# SCH_One.net
KiCad netlist of a schematic drawn in Altium Designer
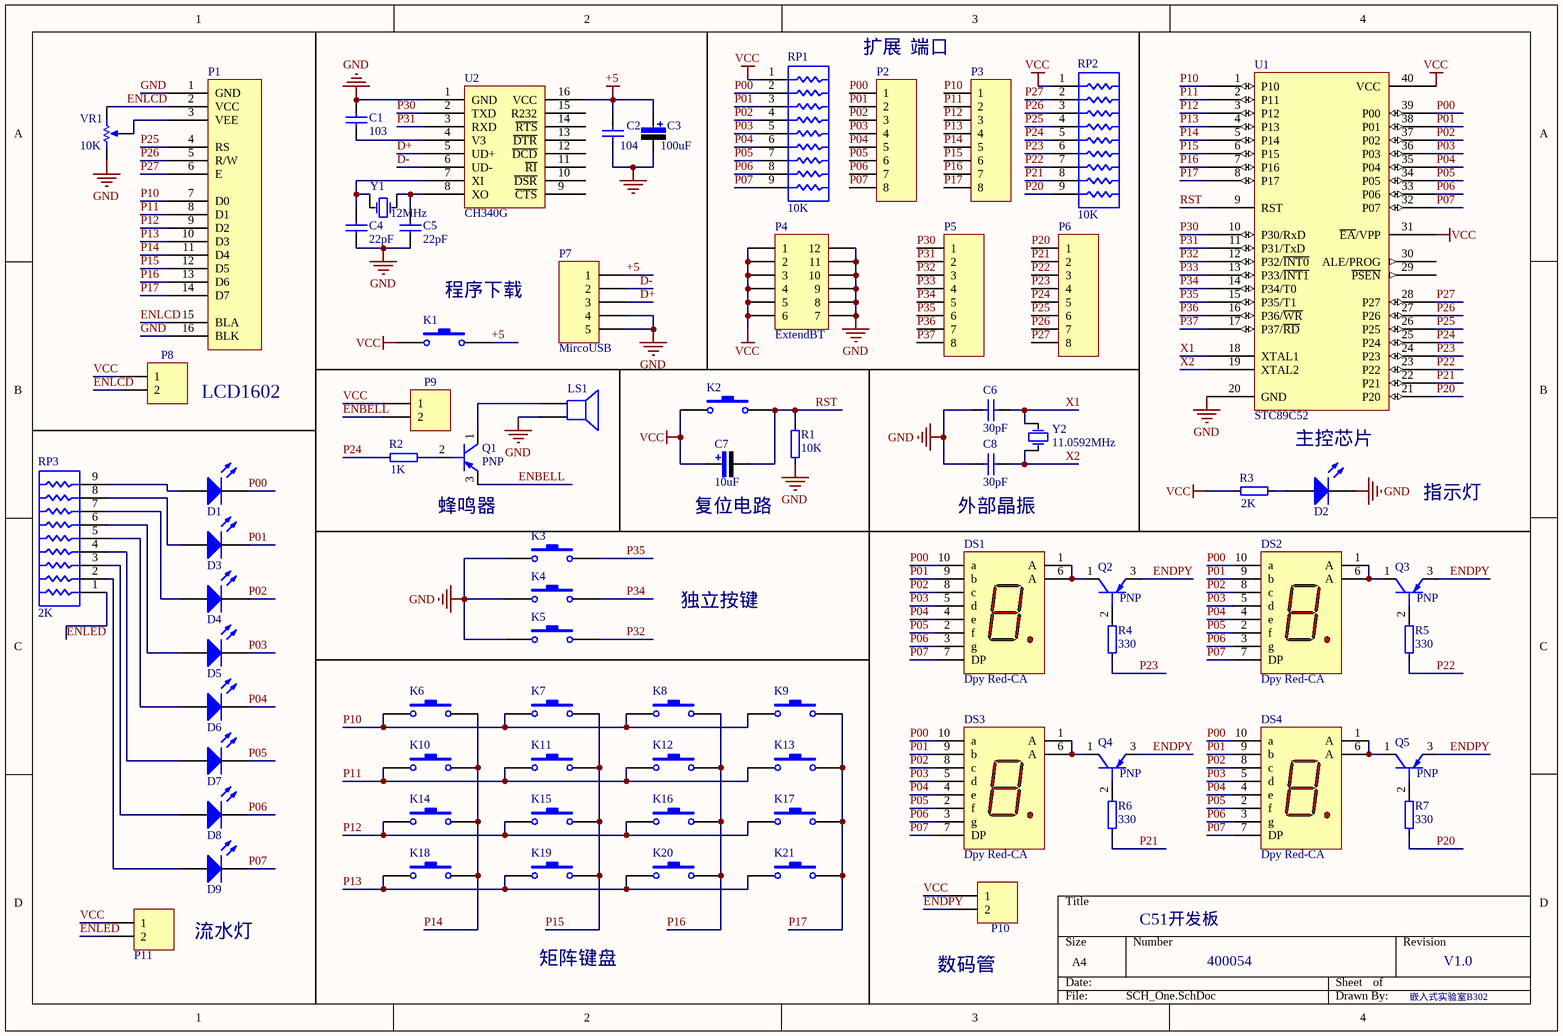
[diagram p0: SCH_One.SchDoc]

(export (version "E")
  (design (tool "Eeschema 10.0.6"))
  (components
    (comp (ref "C1")
      (value "103")
      (footprint "C-RAD")
      (description "电容")
      (libsource (lib "MyLibrary") (part "Cap1"))
    )
    (comp (ref "C2")
      (value "104")
      (footprint "C-RAD")
      (description "电容")
      (libsource (lib "MyLibrary") (part "Cap1"))
    )
    (comp (ref "C3")
      (value "100uF")
      (footprint "CAP_100uF")
      (description "极性电解电容")
      (fields (field (name "Comment") "Cap Pol") (field (name "PUBLISHER") "Altium Limited"))
      (libsource (lib "") (part "Cap Pol_1"))
    )
    (comp (ref "C4")
      (value "22pF")
      (footprint "C-RAD")
      (description "电容")
      (libsource (lib "MyLibrary") (part "Cap1"))
    )
    (comp (ref "C5")
      (value "22pF")
      (footprint "C-RAD")
      (description "电容")
      (libsource (lib "MyLibrary") (part "Cap1"))
    )
    (comp (ref "C6")
      (value "30pF")
      (footprint "C-RAD")
      (description "电容")
      (libsource (lib "MyLibrary") (part "Cap1"))
    )
    (comp (ref "C7")
      (value "10uF")
      (footprint "CAP_10uF")
      (description "极性电解电容")
      (fields (field (name "Comment") "Cap Pol") (field (name "PUBLISHER") "Altium Limited"))
      (libsource (lib "Library") (part "Cap Pol"))
    )
    (comp (ref "C8")
      (value "30pF")
      (footprint "C-RAD")
      (description "电容")
      (libsource (lib "MyLibrary") (part "Cap1"))
    )
    (comp (ref "D1")
      (value "LED0")
      (footprint "LED3")
      (description "发光二极管")
      (fields (field (name "PUBLISHER") "Altium Limited"))
      (libsource (lib "Library") (part "LED0"))
    )
    (comp (ref "D2")
      (value "LED0")
      (footprint "LED3")
      (description "发光二极管")
      (fields (field (name "PUBLISHER") "Altium Limited"))
      (libsource (lib "Library") (part "LED0"))
    )
    (comp (ref "D3")
      (value "LED0")
      (footprint "LED3")
      (description "发光二极管")
      (fields (field (name "PUBLISHER") "Altium Limited"))
      (libsource (lib "Library") (part "LED0"))
    )
    (comp (ref "D4")
      (value "LED0")
      (footprint "LED3")
      (description "发光二极管")
      (fields (field (name "PUBLISHER") "Altium Limited"))
      (libsource (lib "Library") (part "LED0"))
    )
    (comp (ref "D5")
      (value "LED0")
      (footprint "LED3")
      (description "发光二极管")
      (fields (field (name "PUBLISHER") "Altium Limited"))
      (libsource (lib "Library") (part "LED0"))
    )
    (comp (ref "D6")
      (value "LED0")
      (footprint "LED3")
      (description "发光二极管")
      (fields (field (name "PUBLISHER") "Altium Limited"))
      (libsource (lib "Library") (part "LED0"))
    )
    (comp (ref "D7")
      (value "LED0")
      (footprint "LED3")
      (description "发光二极管")
      (fields (field (name "PUBLISHER") "Altium Limited"))
      (libsource (lib "Library") (part "LED0"))
    )
    (comp (ref "D8")
      (value "LED0")
      (footprint "LED3")
      (description "发光二极管")
      (fields (field (name "PUBLISHER") "Altium Limited"))
      (libsource (lib "Library") (part "LED0"))
    )
    (comp (ref "D9")
      (value "LED0")
      (footprint "LED3")
      (description "发光二极管")
      (fields (field (name "PUBLISHER") "Altium Limited"))
      (libsource (lib "Library") (part "LED0"))
    )
    (comp (ref "DS1")
      (value "Dpy Red-CA")
      (footprint "A")
      (description "7.62 mm Black Surface HER 7-Segment Display: CA, RH DP")
      (fields (field (name "PUBLISHER") "Altium Limited"))
      (libsource (lib "Miscellaneous Devices") (part "Dpy Red-CA"))
    )
    (comp (ref "DS2")
      (value "Dpy Red-CA")
      (footprint "A")
      (description "7.62 mm Black Surface HER 7-Segment Display: CA, RH DP")
      (fields (field (name "PUBLISHER") "Altium Limited"))
      (libsource (lib "Miscellaneous Devices") (part "Dpy Red-CA"))
    )
    (comp (ref "DS3")
      (value "Dpy Red-CA")
      (footprint "A")
      (description "7.62 mm Black Surface HER 7-Segment Display: CA, RH DP")
      (fields (field (name "PUBLISHER") "Altium Limited"))
      (libsource (lib "Miscellaneous Devices") (part "Dpy Red-CA"))
    )
    (comp (ref "DS4")
      (value "Dpy Red-CA")
      (footprint "A")
      (description "7.62 mm Black Surface HER 7-Segment Display: CA, RH DP")
      (fields (field (name "PUBLISHER") "Altium Limited"))
      (libsource (lib "Miscellaneous Devices") (part "Dpy Red-CA"))
    )
    (comp (ref "K1")
      (value "Switch1")
      (footprint "KEY-6")
      (description "按键/单刀单掷开关")
      (libsource (lib "MyLibrary") (part "Switch1"))
    )
    (comp (ref "K2")
      (value "Switch1")
      (footprint "SW_PB - 6.5x4.5")
      (description "按键/单刀单掷开关")
      (libsource (lib "MyLibrary") (part "Switch1"))
    )
    (comp (ref "K3")
      (value "Switch1")
      (footprint "SW_PB - 6.5x4.5")
      (description "按键/单刀单掷开关")
      (libsource (lib "MyLibrary") (part "Switch1"))
    )
    (comp (ref "K4")
      (value "Switch1")
      (footprint "SW_PB - 6.5x4.5")
      (description "按键/单刀单掷开关")
      (libsource (lib "MyLibrary") (part "Switch1"))
    )
    (comp (ref "K5")
      (value "Switch1")
      (footprint "SW_PB - 6.5x4.5")
      (description "按键/单刀单掷开关")
      (libsource (lib "MyLibrary") (part "Switch1"))
    )
    (comp (ref "K6")
      (value "Switch1")
      (footprint "SW_PB - 6.5x4.5")
      (description "按键/单刀单掷开关")
      (libsource (lib "MyLibrary") (part "Switch1"))
    )
    (comp (ref "K7")
      (value "Switch1")
      (footprint "SW_PB - 6.5x4.5")
      (description "按键/单刀单掷开关")
      (libsource (lib "MyLibrary") (part "Switch1"))
    )
    (comp (ref "K8")
      (value "Switch1")
      (footprint "SW_PB - 6.5x4.5")
      (description "按键/单刀单掷开关")
      (libsource (lib "MyLibrary") (part "Switch1"))
    )
    (comp (ref "K9")
      (value "Switch1")
      (footprint "SW_PB - 6.5x4.5")
      (description "按键/单刀单掷开关")
      (libsource (lib "MyLibrary") (part "Switch1"))
    )
    (comp (ref "K10")
      (value "Switch1")
      (footprint "SW_PB - 6.5x4.5")
      (description "按键/单刀单掷开关")
      (libsource (lib "MyLibrary") (part "Switch1"))
    )
    (comp (ref "K11")
      (value "Switch1")
      (footprint "SW_PB - 6.5x4.5")
      (description "按键/单刀单掷开关")
      (libsource (lib "MyLibrary") (part "Switch1"))
    )
    (comp (ref "K12")
      (value "Switch1")
      (footprint "SW_PB - 6.5x4.5")
      (description "按键/单刀单掷开关")
      (libsource (lib "MyLibrary") (part "Switch1"))
    )
    (comp (ref "K13")
      (value "Switch1")
      (footprint "SW_PB - 6.5x4.5")
      (description "按键/单刀单掷开关")
      (libsource (lib "MyLibrary") (part "Switch1"))
    )
    (comp (ref "K14")
      (value "Switch1")
      (footprint "SW_PB - 6.5x4.5")
      (description "按键/单刀单掷开关")
      (libsource (lib "MyLibrary") (part "Switch1"))
    )
    (comp (ref "K15")
      (value "Switch1")
      (footprint "SW_PB - 6.5x4.5")
      (description "按键/单刀单掷开关")
      (libsource (lib "MyLibrary") (part "Switch1"))
    )
    (comp (ref "K16")
      (value "Switch1")
      (footprint "SW_PB - 6.5x4.5")
      (description "按键/单刀单掷开关")
      (libsource (lib "MyLibrary") (part "Switch1"))
    )
    (comp (ref "K17")
      (value "Switch1")
      (footprint "SW_PB - 6.5x4.5")
      (description "按键/单刀单掷开关")
      (libsource (lib "MyLibrary") (part "Switch1"))
    )
    (comp (ref "K18")
      (value "Switch1")
      (footprint "SW_PB - 6.5x4.5")
      (description "按键/单刀单掷开关")
      (libsource (lib "MyLibrary") (part "Switch1"))
    )
    (comp (ref "K19")
      (value "Switch1")
      (footprint "SW_PB - 6.5x4.5")
      (description "按键/单刀单掷开关")
      (libsource (lib "MyLibrary") (part "Switch1"))
    )
    (comp (ref "K20")
      (value "Switch1")
      (footprint "SW_PB - 6.5x4.5")
      (description "按键/单刀单掷开关")
      (libsource (lib "MyLibrary") (part "Switch1"))
    )
    (comp (ref "K21")
      (value "Switch1")
      (footprint "SW_PB - 6.5x4.5")
      (description "按键/单刀单掷开关")
      (libsource (lib "MyLibrary") (part "Switch1"))
    )
    (comp (ref "LS1") (value "SPEAKER") (footprint "Beep") (libsource (lib "SCH") (part "SPEAKER")))
    (comp (ref "P1")
      (value "~")
      (footprint "SIP16")
      (description "1602液晶显示器")
      (libsource (lib "MyLibrary") (part "1602"))
    )
    (comp (ref "P2")
      (value "Header 8")
      (footprint "SIP8 - duplicate")
      (description "8PIN")
      (libsource (lib "MyLibrary") (part "Header 8"))
    )
    (comp (ref "P3")
      (value "Header 8")
      (footprint "SIP8 - duplicate")
      (description "8PIN")
      (libsource (lib "MyLibrary") (part "Header 8"))
    )
    (comp (ref "P4")
      (value "ExtendBT")
      (footprint "HDR2x6")
      (description "6PIN两排")
      (libsource (lib "PCB_One") (part "Header 6x2"))
    )
    (comp (ref "P5")
      (value "Header 8")
      (footprint "SIP8")
      (description "8PIN")
      (libsource (lib "MyLibrary") (part "Header 8"))
    )
    (comp (ref "P6")
      (value "Header 8")
      (footprint "SIP8 - duplicate")
      (description "8PIN")
      (libsource (lib "MyLibrary") (part "Header 8"))
    )
    (comp (ref "P7")
      (value "MircoUSB")
      (footprint "MircoUSB")
      (description "5PIN")
      (libsource (lib "MyLibrary") (part "Header 5"))
    )
    (comp (ref "P8")
      (value "Header 2")
      (footprint "HDR2X1_A")
      (description "接插件")
      (fields (field (name "PUBLISHER") "Altium Limited"))
      (libsource (lib "PCB_One") (part "Header 2"))
    )
    (comp (ref "P9")
      (value "Header 2")
      (footprint "HDR2X1_A")
      (description "接插件")
      (fields (field (name "PUBLISHER") "Altium Limited"))
      (libsource (lib "PCB_One") (part "Header 2"))
    )
    (comp (ref "P10")
      (value "Header 2")
      (footprint "HDR2X1_A")
      (description "接插件")
      (fields (field (name "PUBLISHER") "Altium Limited"))
      (libsource (lib "PCB_One") (part "Header 2"))
    )
    (comp (ref "P11")
      (value "Header 2")
      (footprint "HDR2X1_A")
      (description "接插件")
      (fields (field (name "PUBLISHER") "Altium Limited"))
      (libsource (lib "PCB_One") (part "Header 2"))
    )
    (comp (ref "Q1")
      (value "PNP")
      (footprint "TO-92")
      (description "PNP Transistor")
      (libsource (lib "SCH") (part "PNP"))
    )
    (comp (ref "Q2")
      (value "PNP")
      (footprint "TO-92")
      (description "PNP Transistor")
      (libsource (lib "SCH") (part "PNP"))
    )
    (comp (ref "Q3")
      (value "PNP")
      (footprint "TO-92")
      (description "PNP Transistor")
      (libsource (lib "SCH") (part "PNP"))
    )
    (comp (ref "Q4")
      (value "PNP")
      (footprint "TO-92")
      (description "PNP Transistor")
      (libsource (lib "SCH") (part "PNP"))
    )
    (comp (ref "Q5")
      (value "PNP")
      (footprint "TO-92")
      (description "PNP Transistor")
      (libsource (lib "SCH") (part "PNP"))
    )
    (comp (ref "R1")
      (value "10K")
      (footprint "Res_DIP")
      (description "直插电阻")
      (fields (field (name "Comment") "Res"))
      (libsource (lib "MY_Lib") (part "Res"))
    )
    (comp (ref "R2")
      (value "1K")
      (footprint "Res_DIP")
      (description "直插电阻")
      (fields (field (name "Comment") "Res"))
      (libsource (lib "MY_Lib") (part "Res"))
    )
    (comp (ref "R3")
      (value "2K")
      (footprint "Res_DIP")
      (description "直插电阻")
      (fields (field (name "Comment") "Res"))
      (libsource (lib "MY_Lib") (part "Res"))
    )
    (comp (ref "R4")
      (value "330")
      (footprint "Res_DIP")
      (description "直插电阻")
      (fields (field (name "Comment") "Res"))
      (libsource (lib "MY_Lib") (part "Res"))
    )
    (comp (ref "R5")
      (value "330")
      (footprint "Res_DIP")
      (description "直插电阻")
      (fields (field (name "Comment") "Res"))
      (libsource (lib "MY_Lib") (part "Res"))
    )
    (comp (ref "R6")
      (value "330")
      (footprint "Res_DIP")
      (description "直插电阻")
      (fields (field (name "Comment") "Res"))
      (libsource (lib "MY_Lib") (part "Res"))
    )
    (comp (ref "R7")
      (value "330")
      (footprint "Res_DIP")
      (description "直插电阻")
      (fields (field (name "Comment") "Res"))
      (libsource (lib "MY_Lib") (part "Res"))
    )
    (comp (ref "RP1")
      (value "10K")
      (footprint "SIP9 - duplicate")
      (description "9PIN排阻")
      (libsource (lib "MyLibrary") (part "Res Pack2"))
    )
    (comp (ref "RP2")
      (value "10K")
      (footprint "SIP9 - duplicate")
      (description "9PIN排阻")
      (libsource (lib "MyLibrary") (part "Res Pack2"))
    )
    (comp (ref "RP3")
      (value "2K")
      (footprint "SIP9 - duplicate")
      (description "9PIN排阻")
      (libsource (lib "MyLibrary") (part "Res Pack2"))
    )
    (comp (ref "U1")
      (value "STC89C52")
      (footprint "DIP40")
      (description "C51单片机")
      (libsource (lib "MyLibrary") (part "AT89C51"))
    )
    (comp (ref "U2")
      (value "CH340G")
      (footprint "PCB贴片元件封装库:SOP-16")
      (description "USB-SERIAL")
      (libsource (lib "迷宫机器人") (part "CH340G"))
    )
    (comp (ref "VR1")
      (value "10K")
      (footprint "VR4")
      (description "可变电阻器")
      (libsource (lib "MyLibrary") (part "VR"))
    )
    (comp (ref "Y1")
      (value "12MHz")
      (footprint "XTAL1")
      (description "晶振")
      (fields (field (name "Comment") "XTAL") (field (name "PUBLISHER") "Altium Limited"))
      (libsource (lib "Library") (part "XTAL"))
    )
    (comp (ref "Y2")
      (value "11.0592MHz")
      (footprint "XTAL1")
      (description "晶振")
      (fields (field (name "Comment") "XTAL") (field (name "PUBLISHER") "Altium Limited"))
      (libsource (lib "Library") (part "XTAL"))
    )
  )
  (nets
    (net (code "1") (name "+5") (class "Default")
      (node (ref "C2") (pin "2") (pinfunction "2_2") (pintype "passive"))
      (node (ref "C3") (pin "1") (pinfunction "1_1") (pintype "passive"))
      (node (ref "K1") (pin "2") (pinfunction "2_2") (pintype "passive"))
      (node (ref "P7") (pin "1") (pinfunction "1_1") (pintype "passive"))
      (node (ref "U2") (pin "16") (pinfunction "VCC_16") (pintype "passive"))
    )
    (net (code "2") (name "/D+") (class "Default")
      (node (ref "P7") (pin "3") (pinfunction "3_3") (pintype "passive"))
      (node (ref "U2") (pin "5") (pinfunction "UD+_5") (pintype "passive"))
    )
    (net (code "3") (name "/D-") (class "Default")
      (node (ref "P7") (pin "2") (pinfunction "2_2") (pintype "passive"))
      (node (ref "U2") (pin "6") (pinfunction "UD-_6") (pintype "passive"))
    )
    (net (code "4") (name "/ENBELL") (class "Default")
      (node (ref "P9") (pin "2") (pinfunction "2_2") (pintype "passive"))
      (node (ref "Q1") (pin "3") (pinfunction "EMITTER_3") (pintype "open_emitter"))
    )
    (net (code "5") (name "/ENDPY") (class "Default")
      (node (ref "P10") (pin "2") (pinfunction "2_2") (pintype "passive"))
      (node (ref "Q2") (pin "3") (pinfunction "EMITTER_3") (pintype "open_emitter"))
      (node (ref "Q3") (pin "3") (pinfunction "EMITTER_3") (pintype "open_emitter"))
      (node (ref "Q4") (pin "3") (pinfunction "EMITTER_3") (pintype "open_emitter"))
      (node (ref "Q5") (pin "3") (pinfunction "EMITTER_3") (pintype "open_emitter"))
    )
    (net (code "6") (name "/ENLCD") (class "Default")
      (node (ref "P1") (pin "15") (pinfunction "BLA_15") (pintype "passive"))
      (node (ref "P1") (pin "2") (pinfunction "VCC_2") (pintype "passive"))
      (node (ref "P8") (pin "2") (pinfunction "2_2") (pintype "passive"))
      (node (ref "VR1") (pin "1") (pinfunction "TOP_1") (pintype "passive"))
    )
    (net (code "7") (name "/ENLED") (class "Default")
      (node (ref "P11") (pin "2") (pinfunction "2_2") (pintype "passive"))
      (node (ref "RP3") (pin "1") (pinfunction "1_1") (pintype "passive"))
    )
    (net (code "8") (name "/P00") (class "Default")
      (node (ref "D1") (pin "K") (pinfunction "K_K") (pintype "passive"))
      (node (ref "DS1") (pin "10") (pinfunction "a_10") (pintype "passive"))
      (node (ref "DS2") (pin "10") (pinfunction "a_10") (pintype "passive"))
      (node (ref "DS3") (pin "10") (pinfunction "a_10") (pintype "passive"))
      (node (ref "DS4") (pin "10") (pinfunction "a_10") (pintype "passive"))
      (node (ref "P2") (pin "1") (pinfunction "1_1") (pintype "passive"))
      (node (ref "RP1") (pin "2") (pinfunction "2_2") (pintype "passive"))
      (node (ref "U1") (pin "39") (pinfunction "P00_39") (pintype "bidirectional"))
    )
    (net (code "9") (name "/P01") (class "Default")
      (node (ref "D3") (pin "K") (pinfunction "K_K") (pintype "passive"))
      (node (ref "DS1") (pin "9") (pinfunction "b_9") (pintype "passive"))
      (node (ref "DS2") (pin "9") (pinfunction "b_9") (pintype "passive"))
      (node (ref "DS3") (pin "9") (pinfunction "b_9") (pintype "passive"))
      (node (ref "DS4") (pin "9") (pinfunction "b_9") (pintype "passive"))
      (node (ref "P2") (pin "2") (pinfunction "2_2") (pintype "passive"))
      (node (ref "RP1") (pin "3") (pinfunction "3_3") (pintype "passive"))
      (node (ref "U1") (pin "38") (pinfunction "P01_38") (pintype "bidirectional"))
    )
    (net (code "10") (name "/P02") (class "Default")
      (node (ref "D4") (pin "K") (pinfunction "K_K") (pintype "passive"))
      (node (ref "DS1") (pin "8") (pinfunction "c_8") (pintype "passive"))
      (node (ref "DS2") (pin "8") (pinfunction "c_8") (pintype "passive"))
      (node (ref "DS3") (pin "8") (pinfunction "c_8") (pintype "passive"))
      (node (ref "DS4") (pin "8") (pinfunction "c_8") (pintype "passive"))
      (node (ref "P2") (pin "3") (pinfunction "3_3") (pintype "passive"))
      (node (ref "RP1") (pin "4") (pinfunction "4_4") (pintype "passive"))
      (node (ref "U1") (pin "37") (pinfunction "P02_37") (pintype "bidirectional"))
    )
    (net (code "11") (name "/P03") (class "Default")
      (node (ref "D5") (pin "K") (pinfunction "K_K") (pintype "passive"))
      (node (ref "DS1") (pin "5") (pinfunction "d_5") (pintype "passive"))
      (node (ref "DS2") (pin "5") (pinfunction "d_5") (pintype "passive"))
      (node (ref "DS3") (pin "5") (pinfunction "d_5") (pintype "passive"))
      (node (ref "DS4") (pin "5") (pinfunction "d_5") (pintype "passive"))
      (node (ref "P2") (pin "4") (pinfunction "4_4") (pintype "passive"))
      (node (ref "RP1") (pin "5") (pinfunction "5_5") (pintype "passive"))
      (node (ref "U1") (pin "36") (pinfunction "P03_36") (pintype "bidirectional"))
    )
    (net (code "12") (name "/P04") (class "Default")
      (node (ref "D6") (pin "K") (pinfunction "K_K") (pintype "passive"))
      (node (ref "DS1") (pin "4") (pinfunction "e_4") (pintype "passive"))
      (node (ref "DS2") (pin "4") (pinfunction "e_4") (pintype "passive"))
      (node (ref "DS3") (pin "4") (pinfunction "e_4") (pintype "passive"))
      (node (ref "DS4") (pin "4") (pinfunction "e_4") (pintype "passive"))
      (node (ref "P2") (pin "5") (pinfunction "5_5") (pintype "passive"))
      (node (ref "RP1") (pin "6") (pinfunction "6_6") (pintype "passive"))
      (node (ref "U1") (pin "35") (pinfunction "P04_35") (pintype "bidirectional"))
    )
    (net (code "13") (name "/P05") (class "Default")
      (node (ref "D7") (pin "K") (pinfunction "K_K") (pintype "passive"))
      (node (ref "DS1") (pin "2") (pinfunction "f_2") (pintype "passive"))
      (node (ref "DS2") (pin "2") (pinfunction "f_2") (pintype "passive"))
      (node (ref "DS3") (pin "2") (pinfunction "f_2") (pintype "passive"))
      (node (ref "DS4") (pin "2") (pinfunction "f_2") (pintype "passive"))
      (node (ref "P2") (pin "6") (pinfunction "6_6") (pintype "passive"))
      (node (ref "RP1") (pin "7") (pinfunction "7_7") (pintype "passive"))
      (node (ref "U1") (pin "34") (pinfunction "P05_34") (pintype "bidirectional"))
    )
    (net (code "14") (name "/P06") (class "Default")
      (node (ref "D8") (pin "K") (pinfunction "K_K") (pintype "passive"))
      (node (ref "DS1") (pin "3") (pinfunction "g_3") (pintype "passive"))
      (node (ref "DS2") (pin "3") (pinfunction "g_3") (pintype "passive"))
      (node (ref "DS3") (pin "3") (pinfunction "g_3") (pintype "passive"))
      (node (ref "DS4") (pin "3") (pinfunction "g_3") (pintype "passive"))
      (node (ref "P2") (pin "7") (pinfunction "7_7") (pintype "passive"))
      (node (ref "RP1") (pin "8") (pinfunction "8_8") (pintype "passive"))
      (node (ref "U1") (pin "33") (pinfunction "P06_33") (pintype "bidirectional"))
    )
    (net (code "15") (name "/P07") (class "Default")
      (node (ref "D9") (pin "K") (pinfunction "K_K") (pintype "passive"))
      (node (ref "DS1") (pin "7") (pinfunction "DP_7") (pintype "passive"))
      (node (ref "DS2") (pin "7") (pinfunction "DP_7") (pintype "passive"))
      (node (ref "DS3") (pin "7") (pinfunction "DP_7") (pintype "passive"))
      (node (ref "DS4") (pin "7") (pinfunction "DP_7") (pintype "passive"))
      (node (ref "P2") (pin "8") (pinfunction "8_8") (pintype "passive"))
      (node (ref "RP1") (pin "9") (pinfunction "9_9") (pintype "passive"))
      (node (ref "U1") (pin "32") (pinfunction "P07_32") (pintype "bidirectional"))
    )
    (net (code "16") (name "/P10") (class "Default")
      (node (ref "K6") (pin "1") (pinfunction "1_1") (pintype "passive"))
      (node (ref "K7") (pin "1") (pinfunction "1_1") (pintype "passive"))
      (node (ref "K8") (pin "1") (pinfunction "1_1") (pintype "passive"))
      (node (ref "K9") (pin "1") (pinfunction "1_1") (pintype "passive"))
      (node (ref "P1") (pin "7") (pinfunction "D0_7") (pintype "passive"))
      (node (ref "P3") (pin "1") (pinfunction "1_1") (pintype "passive"))
      (node (ref "U1") (pin "1") (pinfunction "P10_1") (pintype "bidirectional"))
    )
    (net (code "17") (name "/P11") (class "Default")
      (node (ref "K10") (pin "1") (pinfunction "1_1") (pintype "passive"))
      (node (ref "K11") (pin "1") (pinfunction "1_1") (pintype "passive"))
      (node (ref "K12") (pin "1") (pinfunction "1_1") (pintype "passive"))
      (node (ref "K13") (pin "1") (pinfunction "1_1") (pintype "passive"))
      (node (ref "P1") (pin "8") (pinfunction "D1_8") (pintype "passive"))
      (node (ref "P3") (pin "2") (pinfunction "2_2") (pintype "passive"))
      (node (ref "U1") (pin "2") (pinfunction "P11_2") (pintype "bidirectional"))
    )
    (net (code "18") (name "/P12") (class "Default")
      (node (ref "K14") (pin "1") (pinfunction "1_1") (pintype "passive"))
      (node (ref "K15") (pin "1") (pinfunction "1_1") (pintype "passive"))
      (node (ref "K16") (pin "1") (pinfunction "1_1") (pintype "passive"))
      (node (ref "K17") (pin "1") (pinfunction "1_1") (pintype "passive"))
      (node (ref "P1") (pin "9") (pinfunction "D2_9") (pintype "passive"))
      (node (ref "P3") (pin "3") (pinfunction "3_3") (pintype "passive"))
      (node (ref "U1") (pin "3") (pinfunction "P12_3") (pintype "bidirectional"))
    )
    (net (code "19") (name "/P13") (class "Default")
      (node (ref "K18") (pin "1") (pinfunction "1_1") (pintype "passive"))
      (node (ref "K19") (pin "1") (pinfunction "1_1") (pintype "passive"))
      (node (ref "K20") (pin "1") (pinfunction "1_1") (pintype "passive"))
      (node (ref "K21") (pin "1") (pinfunction "1_1") (pintype "passive"))
      (node (ref "P1") (pin "10") (pinfunction "D3_10") (pintype "passive"))
      (node (ref "P3") (pin "4") (pinfunction "4_4") (pintype "passive"))
      (node (ref "U1") (pin "4") (pinfunction "P13_4") (pintype "bidirectional"))
    )
    (net (code "20") (name "/P14") (class "Default")
      (node (ref "K10") (pin "2") (pinfunction "2_2") (pintype "passive"))
      (node (ref "K14") (pin "2") (pinfunction "2_2") (pintype "passive"))
      (node (ref "K18") (pin "2") (pinfunction "2_2") (pintype "passive"))
      (node (ref "K6") (pin "2") (pinfunction "2_2") (pintype "passive"))
      (node (ref "P1") (pin "11") (pinfunction "D4_11") (pintype "passive"))
      (node (ref "P3") (pin "5") (pinfunction "5_5") (pintype "passive"))
      (node (ref "U1") (pin "5") (pinfunction "P14_5") (pintype "bidirectional"))
    )
    (net (code "21") (name "/P15") (class "Default")
      (node (ref "K11") (pin "2") (pinfunction "2_2") (pintype "passive"))
      (node (ref "K15") (pin "2") (pinfunction "2_2") (pintype "passive"))
      (node (ref "K19") (pin "2") (pinfunction "2_2") (pintype "passive"))
      (node (ref "K7") (pin "2") (pinfunction "2_2") (pintype "passive"))
      (node (ref "P1") (pin "12") (pinfunction "D5_12") (pintype "passive"))
      (node (ref "P3") (pin "6") (pinfunction "6_6") (pintype "passive"))
      (node (ref "U1") (pin "6") (pinfunction "P15_6") (pintype "bidirectional"))
    )
    (net (code "22") (name "/P16") (class "Default")
      (node (ref "K12") (pin "2") (pinfunction "2_2") (pintype "passive"))
      (node (ref "K16") (pin "2") (pinfunction "2_2") (pintype "passive"))
      (node (ref "K20") (pin "2") (pinfunction "2_2") (pintype "passive"))
      (node (ref "K8") (pin "2") (pinfunction "2_2") (pintype "passive"))
      (node (ref "P1") (pin "13") (pinfunction "D6_13") (pintype "passive"))
      (node (ref "P3") (pin "7") (pinfunction "7_7") (pintype "passive"))
      (node (ref "U1") (pin "7") (pinfunction "P16_7") (pintype "bidirectional"))
    )
    (net (code "23") (name "/P17") (class "Default")
      (node (ref "K13") (pin "2") (pinfunction "2_2") (pintype "passive"))
      (node (ref "K17") (pin "2") (pinfunction "2_2") (pintype "passive"))
      (node (ref "K21") (pin "2") (pinfunction "2_2") (pintype "passive"))
      (node (ref "K9") (pin "2") (pinfunction "2_2") (pintype "passive"))
      (node (ref "P1") (pin "14") (pinfunction "D7_14") (pintype "passive"))
      (node (ref "P3") (pin "8") (pinfunction "8_8") (pintype "passive"))
      (node (ref "U1") (pin "8") (pinfunction "P17_8") (pintype "bidirectional"))
    )
    (net (code "24") (name "/P20") (class "Default")
      (node (ref "P6") (pin "1") (pinfunction "1_1") (pintype "passive"))
      (node (ref "R7") (pin "1") (pinfunction "1_1") (pintype "passive"))
      (node (ref "RP2") (pin "9") (pinfunction "9_9") (pintype "passive"))
      (node (ref "U1") (pin "21") (pinfunction "P20_21") (pintype "bidirectional"))
    )
    (net (code "25") (name "/P21") (class "Default")
      (node (ref "P6") (pin "2") (pinfunction "2_2") (pintype "passive"))
      (node (ref "R6") (pin "1") (pinfunction "1_1") (pintype "passive"))
      (node (ref "RP2") (pin "8") (pinfunction "8_8") (pintype "passive"))
      (node (ref "U1") (pin "22") (pinfunction "P21_22") (pintype "bidirectional"))
    )
    (net (code "26") (name "/P22") (class "Default")
      (node (ref "P6") (pin "3") (pinfunction "3_3") (pintype "passive"))
      (node (ref "R5") (pin "1") (pinfunction "1_1") (pintype "passive"))
      (node (ref "RP2") (pin "7") (pinfunction "7_7") (pintype "passive"))
      (node (ref "U1") (pin "23") (pinfunction "P22_23") (pintype "bidirectional"))
    )
    (net (code "27") (name "/P23") (class "Default")
      (node (ref "P6") (pin "4") (pinfunction "4_4") (pintype "passive"))
      (node (ref "R4") (pin "1") (pinfunction "1_1") (pintype "passive"))
      (node (ref "RP2") (pin "6") (pinfunction "6_6") (pintype "passive"))
      (node (ref "U1") (pin "24") (pinfunction "P23_24") (pintype "bidirectional"))
    )
    (net (code "28") (name "/P24") (class "Default")
      (node (ref "P6") (pin "5") (pinfunction "5_5") (pintype "passive"))
      (node (ref "R2") (pin "1") (pinfunction "1_1") (pintype "passive"))
      (node (ref "RP2") (pin "5") (pinfunction "5_5") (pintype "passive"))
      (node (ref "U1") (pin "25") (pinfunction "P24_25") (pintype "bidirectional"))
    )
    (net (code "29") (name "/P25") (class "Default")
      (node (ref "P1") (pin "4") (pinfunction "RS_4") (pintype "passive"))
      (node (ref "P6") (pin "6") (pinfunction "6_6") (pintype "passive"))
      (node (ref "RP2") (pin "4") (pinfunction "4_4") (pintype "passive"))
      (node (ref "U1") (pin "26") (pinfunction "P25_26") (pintype "bidirectional"))
    )
    (net (code "30") (name "/P26") (class "Default")
      (node (ref "P1") (pin "5") (pinfunction "R/W_5") (pintype "passive"))
      (node (ref "P6") (pin "7") (pinfunction "7_7") (pintype "passive"))
      (node (ref "RP2") (pin "3") (pinfunction "3_3") (pintype "passive"))
      (node (ref "U1") (pin "27") (pinfunction "P26_27") (pintype "bidirectional"))
    )
    (net (code "31") (name "/P27") (class "Default")
      (node (ref "P1") (pin "6") (pinfunction "E_6") (pintype "passive"))
      (node (ref "P6") (pin "8") (pinfunction "8_8") (pintype "passive"))
      (node (ref "RP2") (pin "2") (pinfunction "2_2") (pintype "passive"))
      (node (ref "U1") (pin "28") (pinfunction "P27_28") (pintype "bidirectional"))
    )
    (net (code "32") (name "/P30") (class "Default")
      (node (ref "P5") (pin "1") (pinfunction "1_1") (pintype "passive"))
      (node (ref "U1") (pin "10") (pinfunction "P30/RxD_10") (pintype "bidirectional"))
      (node (ref "U2") (pin "2") (pinfunction "TXD_2") (pintype "passive"))
    )
    (net (code "33") (name "/P31") (class "Default")
      (node (ref "P5") (pin "2") (pinfunction "2_2") (pintype "passive"))
      (node (ref "U1") (pin "11") (pinfunction "P31/TxD_11") (pintype "bidirectional"))
      (node (ref "U2") (pin "3") (pinfunction "RXD_3") (pintype "passive"))
    )
    (net (code "34") (name "/P32") (class "Default")
      (node (ref "K5") (pin "2") (pinfunction "2_2") (pintype "passive"))
      (node (ref "P5") (pin "3") (pinfunction "3_3") (pintype "passive"))
      (node (ref "U1") (pin "12") (pinfunction "P32/~{INT0}_12") (pintype "bidirectional"))
    )
    (net (code "35") (name "/P33") (class "Default")
      (node (ref "P5") (pin "4") (pinfunction "4_4") (pintype "passive"))
      (node (ref "U1") (pin "13") (pinfunction "P33/~{INT1}_13") (pintype "bidirectional"))
    )
    (net (code "36") (name "/P34") (class "Default")
      (node (ref "K4") (pin "2") (pinfunction "2_2") (pintype "passive"))
      (node (ref "P5") (pin "5") (pinfunction "5_5") (pintype "passive"))
      (node (ref "U1") (pin "14") (pinfunction "P34/T0_14") (pintype "bidirectional"))
    )
    (net (code "37") (name "/P35") (class "Default")
      (node (ref "K3") (pin "2") (pinfunction "2_2") (pintype "passive"))
      (node (ref "P5") (pin "6") (pinfunction "6_6") (pintype "passive"))
      (node (ref "U1") (pin "15") (pinfunction "P35/T1_15") (pintype "bidirectional"))
    )
    (net (code "38") (name "/P36") (class "Default")
      (node (ref "P5") (pin "7") (pinfunction "7_7") (pintype "passive"))
      (node (ref "U1") (pin "16") (pinfunction "P36/~{WR}_16") (pintype "bidirectional"))
    )
    (net (code "39") (name "/P37") (class "Default")
      (node (ref "P5") (pin "8") (pinfunction "8_8") (pintype "passive"))
      (node (ref "U1") (pin "17") (pinfunction "P37/~{RD}_17") (pintype "bidirectional"))
    )
    (net (code "40") (name "/RST") (class "Default")
      (node (ref "C7") (pin "2") (pinfunction "2_2") (pintype "passive"))
      (node (ref "K2") (pin "2") (pinfunction "2_2") (pintype "passive"))
      (node (ref "R1") (pin "2") (pinfunction "2_2") (pintype "passive"))
      (node (ref "U1") (pin "9") (pinfunction "RST_9") (pintype "passive"))
    )
    (net (code "41") (name "/X1") (class "Default")
      (node (ref "C6") (pin "2") (pinfunction "2_2") (pintype "passive"))
      (node (ref "U1") (pin "18") (pinfunction "XTAL1_18") (pintype "passive"))
      (node (ref "Y2") (pin "1") (pinfunction "OSC1_1") (pintype "passive"))
    )
    (net (code "42") (name "/X2") (class "Default")
      (node (ref "C8") (pin "2") (pinfunction "2_2") (pintype "passive"))
      (node (ref "U1") (pin "19") (pinfunction "XTAL2_19") (pintype "passive"))
      (node (ref "Y2") (pin "2") (pinfunction "OSC2_2") (pintype "passive"))
    )
    (net (code "43") (name "GND") (class "Default")
      (node (ref "C1") (pin "2") (pinfunction "2_2") (pintype "passive"))
      (node (ref "C2") (pin "1") (pinfunction "1_1") (pintype "passive"))
      (node (ref "C3") (pin "2") (pinfunction "2_2") (pintype "passive"))
      (node (ref "C4") (pin "1") (pinfunction "1_1") (pintype "passive"))
      (node (ref "C5") (pin "1") (pinfunction "1_1") (pintype "passive"))
      (node (ref "C6") (pin "1") (pinfunction "1_1") (pintype "passive"))
      (node (ref "C8") (pin "1") (pinfunction "1_1") (pintype "passive"))
      (node (ref "D2") (pin "K") (pinfunction "K_K") (pintype "passive"))
      (node (ref "K3") (pin "1") (pinfunction "1_1") (pintype "passive"))
      (node (ref "K4") (pin "1") (pinfunction "1_1") (pintype "passive"))
      (node (ref "K5") (pin "1") (pinfunction "1_1") (pintype "passive"))
      (node (ref "LS1") (pin "2") (pinfunction "2_2") (pintype "passive"))
      (node (ref "P1") (pin "1") (pinfunction "GND_1") (pintype "passive"))
      (node (ref "P1") (pin "16") (pinfunction "BLK_16") (pintype "passive"))
      (node (ref "P4") (pin "10") (pinfunction "10_10") (pintype "passive"))
      (node (ref "P4") (pin "11") (pinfunction "11_11") (pintype "passive"))
      (node (ref "P4") (pin "12") (pinfunction "12_12") (pintype "passive"))
      (node (ref "P4") (pin "7") (pinfunction "7_7") (pintype "passive"))
      (node (ref "P4") (pin "8") (pinfunction "8_8") (pintype "passive"))
      (node (ref "P4") (pin "9") (pinfunction "9_9") (pintype "passive"))
      (node (ref "P7") (pin "4") (pinfunction "4_4") (pintype "passive"))
      (node (ref "P7") (pin "5") (pinfunction "5_5") (pintype "passive"))
      (node (ref "R1") (pin "1") (pinfunction "1_1") (pintype "passive"))
      (node (ref "U1") (pin "20") (pinfunction "GND_20") (pintype "passive"))
      (node (ref "U2") (pin "1") (pinfunction "GND_1") (pintype "passive"))
      (node (ref "VR1") (pin "3") (pinfunction "BOT_3") (pintype "passive"))
    )
    (net (code "44") (name "Net-(D1-PadA)") (class "Default")
      (node (ref "D1") (pin "A") (pinfunction "A_A") (pintype "passive"))
      (node (ref "RP3") (pin "9") (pinfunction "9_9") (pintype "passive"))
    )
    (net (code "45") (name "Net-(D2-PadA)") (class "Default")
      (node (ref "D2") (pin "A") (pinfunction "A_A") (pintype "passive"))
      (node (ref "R3") (pin "2") (pinfunction "2_2") (pintype "passive"))
    )
    (net (code "46") (name "Net-(D3-PadA)") (class "Default")
      (node (ref "D3") (pin "A") (pinfunction "A_A") (pintype "passive"))
      (node (ref "RP3") (pin "8") (pinfunction "8_8") (pintype "passive"))
    )
    (net (code "47") (name "Net-(D4-PadA)") (class "Default")
      (node (ref "D4") (pin "A") (pinfunction "A_A") (pintype "passive"))
      (node (ref "RP3") (pin "7") (pinfunction "7_7") (pintype "passive"))
    )
    (net (code "48") (name "Net-(D5-PadA)") (class "Default")
      (node (ref "D5") (pin "A") (pinfunction "A_A") (pintype "passive"))
      (node (ref "RP3") (pin "6") (pinfunction "6_6") (pintype "passive"))
    )
    (net (code "49") (name "Net-(D6-PadA)") (class "Default")
      (node (ref "D6") (pin "A") (pinfunction "A_A") (pintype "passive"))
      (node (ref "RP3") (pin "5") (pinfunction "5_5") (pintype "passive"))
    )
    (net (code "50") (name "Net-(D7-PadA)") (class "Default")
      (node (ref "D7") (pin "A") (pinfunction "A_A") (pintype "passive"))
      (node (ref "RP3") (pin "4") (pinfunction "4_4") (pintype "passive"))
    )
    (net (code "51") (name "Net-(D8-PadA)") (class "Default")
      (node (ref "D8") (pin "A") (pinfunction "A_A") (pintype "passive"))
      (node (ref "RP3") (pin "3") (pinfunction "3_3") (pintype "passive"))
    )
    (net (code "52") (name "Net-(D9-PadA)") (class "Default")
      (node (ref "D9") (pin "A") (pinfunction "A_A") (pintype "passive"))
      (node (ref "RP3") (pin "2") (pinfunction "2_2") (pintype "passive"))
    )
    (net (code "53") (name "Net-(P1-VEE)") (class "Default")
      (node (ref "P1") (pin "3") (pinfunction "VEE_3") (pintype "passive"))
      (node (ref "VR1") (pin "2") (pinfunction "TAP_2") (pintype "passive"))
    )
    (net (code "54") (name "Net-(Q1-BASE)") (class "Default")
      (node (ref "Q1") (pin "2") (pinfunction "BASE_2") (pintype "open_collector"))
      (node (ref "R2") (pin "2") (pinfunction "2_2") (pintype "passive"))
    )
    (net (code "55") (name "Net-(Q1-COLLECTOR)") (class "Default")
      (node (ref "LS1") (pin "1") (pinfunction "1_1") (pintype "passive"))
      (node (ref "Q1") (pin "1") (pinfunction "COLLECTOR_1") (pintype "open_collector"))
    )
    (net (code "56") (name "Net-(Q2-BASE)") (class "Default")
      (node (ref "Q2") (pin "2") (pinfunction "BASE_2") (pintype "open_collector"))
      (node (ref "R4") (pin "2") (pinfunction "2_2") (pintype "passive"))
    )
    (net (code "57") (name "Net-(Q2-COLLECTOR)") (class "Default")
      (node (ref "DS1") (pin "1") (pinfunction "A_1") (pintype "passive"))
      (node (ref "DS1") (pin "6") (pinfunction "A_6") (pintype "passive"))
      (node (ref "Q2") (pin "1") (pinfunction "COLLECTOR_1") (pintype "open_collector"))
    )
    (net (code "58") (name "Net-(Q3-BASE)") (class "Default")
      (node (ref "Q3") (pin "2") (pinfunction "BASE_2") (pintype "open_collector"))
      (node (ref "R5") (pin "2") (pinfunction "2_2") (pintype "passive"))
    )
    (net (code "59") (name "Net-(Q3-COLLECTOR)") (class "Default")
      (node (ref "DS2") (pin "1") (pinfunction "A_1") (pintype "passive"))
      (node (ref "DS2") (pin "6") (pinfunction "A_6") (pintype "passive"))
      (node (ref "Q3") (pin "1") (pinfunction "COLLECTOR_1") (pintype "open_collector"))
    )
    (net (code "60") (name "Net-(Q4-BASE)") (class "Default")
      (node (ref "Q4") (pin "2") (pinfunction "BASE_2") (pintype "open_collector"))
      (node (ref "R6") (pin "2") (pinfunction "2_2") (pintype "passive"))
    )
    (net (code "61") (name "Net-(Q4-COLLECTOR)") (class "Default")
      (node (ref "DS3") (pin "1") (pinfunction "A_1") (pintype "passive"))
      (node (ref "DS3") (pin "6") (pinfunction "A_6") (pintype "passive"))
      (node (ref "Q4") (pin "1") (pinfunction "COLLECTOR_1") (pintype "open_collector"))
    )
    (net (code "62") (name "Net-(Q5-BASE)") (class "Default")
      (node (ref "Q5") (pin "2") (pinfunction "BASE_2") (pintype "open_collector"))
      (node (ref "R7") (pin "2") (pinfunction "2_2") (pintype "passive"))
    )
    (net (code "63") (name "Net-(Q5-COLLECTOR)") (class "Default")
      (node (ref "DS4") (pin "1") (pinfunction "A_1") (pintype "passive"))
      (node (ref "DS4") (pin "6") (pinfunction "A_6") (pintype "passive"))
      (node (ref "Q5") (pin "1") (pinfunction "COLLECTOR_1") (pintype "open_collector"))
    )
    (net (code "64") (name "Net-(U2-V3)") (class "Default")
      (node (ref "C1") (pin "1") (pinfunction "1_1") (pintype "passive"))
      (node (ref "U2") (pin "4") (pinfunction "V3_4") (pintype "passive"))
    )
    (net (code "65") (name "Net-(U2-XI)") (class "Default")
      (node (ref "C4") (pin "2") (pinfunction "2_2") (pintype "passive"))
      (node (ref "U2") (pin "7") (pinfunction "XI_7") (pintype "passive"))
      (node (ref "Y1") (pin "2") (pinfunction "OSC2_2") (pintype "passive"))
    )
    (net (code "66") (name "Net-(U2-XO)") (class "Default")
      (node (ref "C5") (pin "2") (pinfunction "2_2") (pintype "passive"))
      (node (ref "U2") (pin "8") (pinfunction "XO_8") (pintype "passive"))
      (node (ref "Y1") (pin "1") (pinfunction "OSC1_1") (pintype "passive"))
    )
    (net (code "67") (name "VCC") (class "Default")
      (node (ref "C7") (pin "1") (pinfunction "1_1") (pintype "passive"))
      (node (ref "K1") (pin "1") (pinfunction "1_1") (pintype "passive"))
      (node (ref "K2") (pin "1") (pinfunction "1_1") (pintype "passive"))
      (node (ref "P10") (pin "1") (pinfunction "1_1") (pintype "passive"))
      (node (ref "P11") (pin "1") (pinfunction "1_1") (pintype "passive"))
      (node (ref "P4") (pin "1") (pinfunction "1_1") (pintype "passive"))
      (node (ref "P4") (pin "2") (pinfunction "2_2") (pintype "passive"))
      (node (ref "P4") (pin "3") (pinfunction "3_3") (pintype "passive"))
      (node (ref "P4") (pin "4") (pinfunction "4_4") (pintype "passive"))
      (node (ref "P4") (pin "5") (pinfunction "5_5") (pintype "passive"))
      (node (ref "P4") (pin "6") (pinfunction "6_6") (pintype "passive"))
      (node (ref "P8") (pin "1") (pinfunction "1_1") (pintype "passive"))
      (node (ref "P9") (pin "1") (pinfunction "1_1") (pintype "passive"))
      (node (ref "R3") (pin "1") (pinfunction "1_1") (pintype "passive"))
      (node (ref "RP1") (pin "1") (pinfunction "1_1") (pintype "passive"))
      (node (ref "RP2") (pin "1") (pinfunction "1_1") (pintype "passive"))
      (node (ref "U1") (pin "31") (pinfunction "~{EA}/VPP_31") (pintype "passive"))
      (node (ref "U1") (pin "40") (pinfunction "VCC_40") (pintype "passive"))
    )
    (net (code "68") (name "unconnected-(U1-ALE{slash}PROG-Pad30)") (class "Default")
      (node (ref "U1") (pin "30") (pinfunction "ALE/PROG_30") (pintype "output"))
    )
    (net (code "69") (name "unconnected-(U1-~{PSEN}-Pad29)") (class "Default")
      (node (ref "U1") (pin "29") (pinfunction "~{PSEN}_29") (pintype "output"))
    )
    (net (code "70") (name "unconnected-(U2-R232-Pad15)") (class "Default")
      (node (ref "U2") (pin "15") (pinfunction "R232_15") (pintype "passive"))
    )
    (net (code "71") (name "unconnected-(U2-~{CTS}-Pad9)") (class "Default")
      (node (ref "U2") (pin "9") (pinfunction "~{CTS}_9") (pintype "passive"))
    )
    (net (code "72") (name "unconnected-(U2-~{DCD}-Pad12)") (class "Default")
      (node (ref "U2") (pin "12") (pinfunction "~{DCD}_12") (pintype "passive"))
    )
    (net (code "73") (name "unconnected-(U2-~{DSR}-Pad10)") (class "Default")
      (node (ref "U2") (pin "10") (pinfunction "~{DSR}_10") (pintype "passive"))
    )
    (net (code "74") (name "unconnected-(U2-~{DTR}-Pad13)") (class "Default")
      (node (ref "U2") (pin "13") (pinfunction "~{DTR}_13") (pintype "passive"))
    )
    (net (code "75") (name "unconnected-(U2-~{RI}-Pad11)") (class "Default")
      (node (ref "U2") (pin "11") (pinfunction "~{RI}_11") (pintype "passive"))
    )
    (net (code "76") (name "unconnected-(U2-~{RTS}-Pad14)") (class "Default")
      (node (ref "U2") (pin "14") (pinfunction "~{RTS}_14") (pintype "passive"))
    )
  )
)
